# RPi_Extension_EtherCat_Host.net
KiCad netlist of a schematic drawn in EAGLE
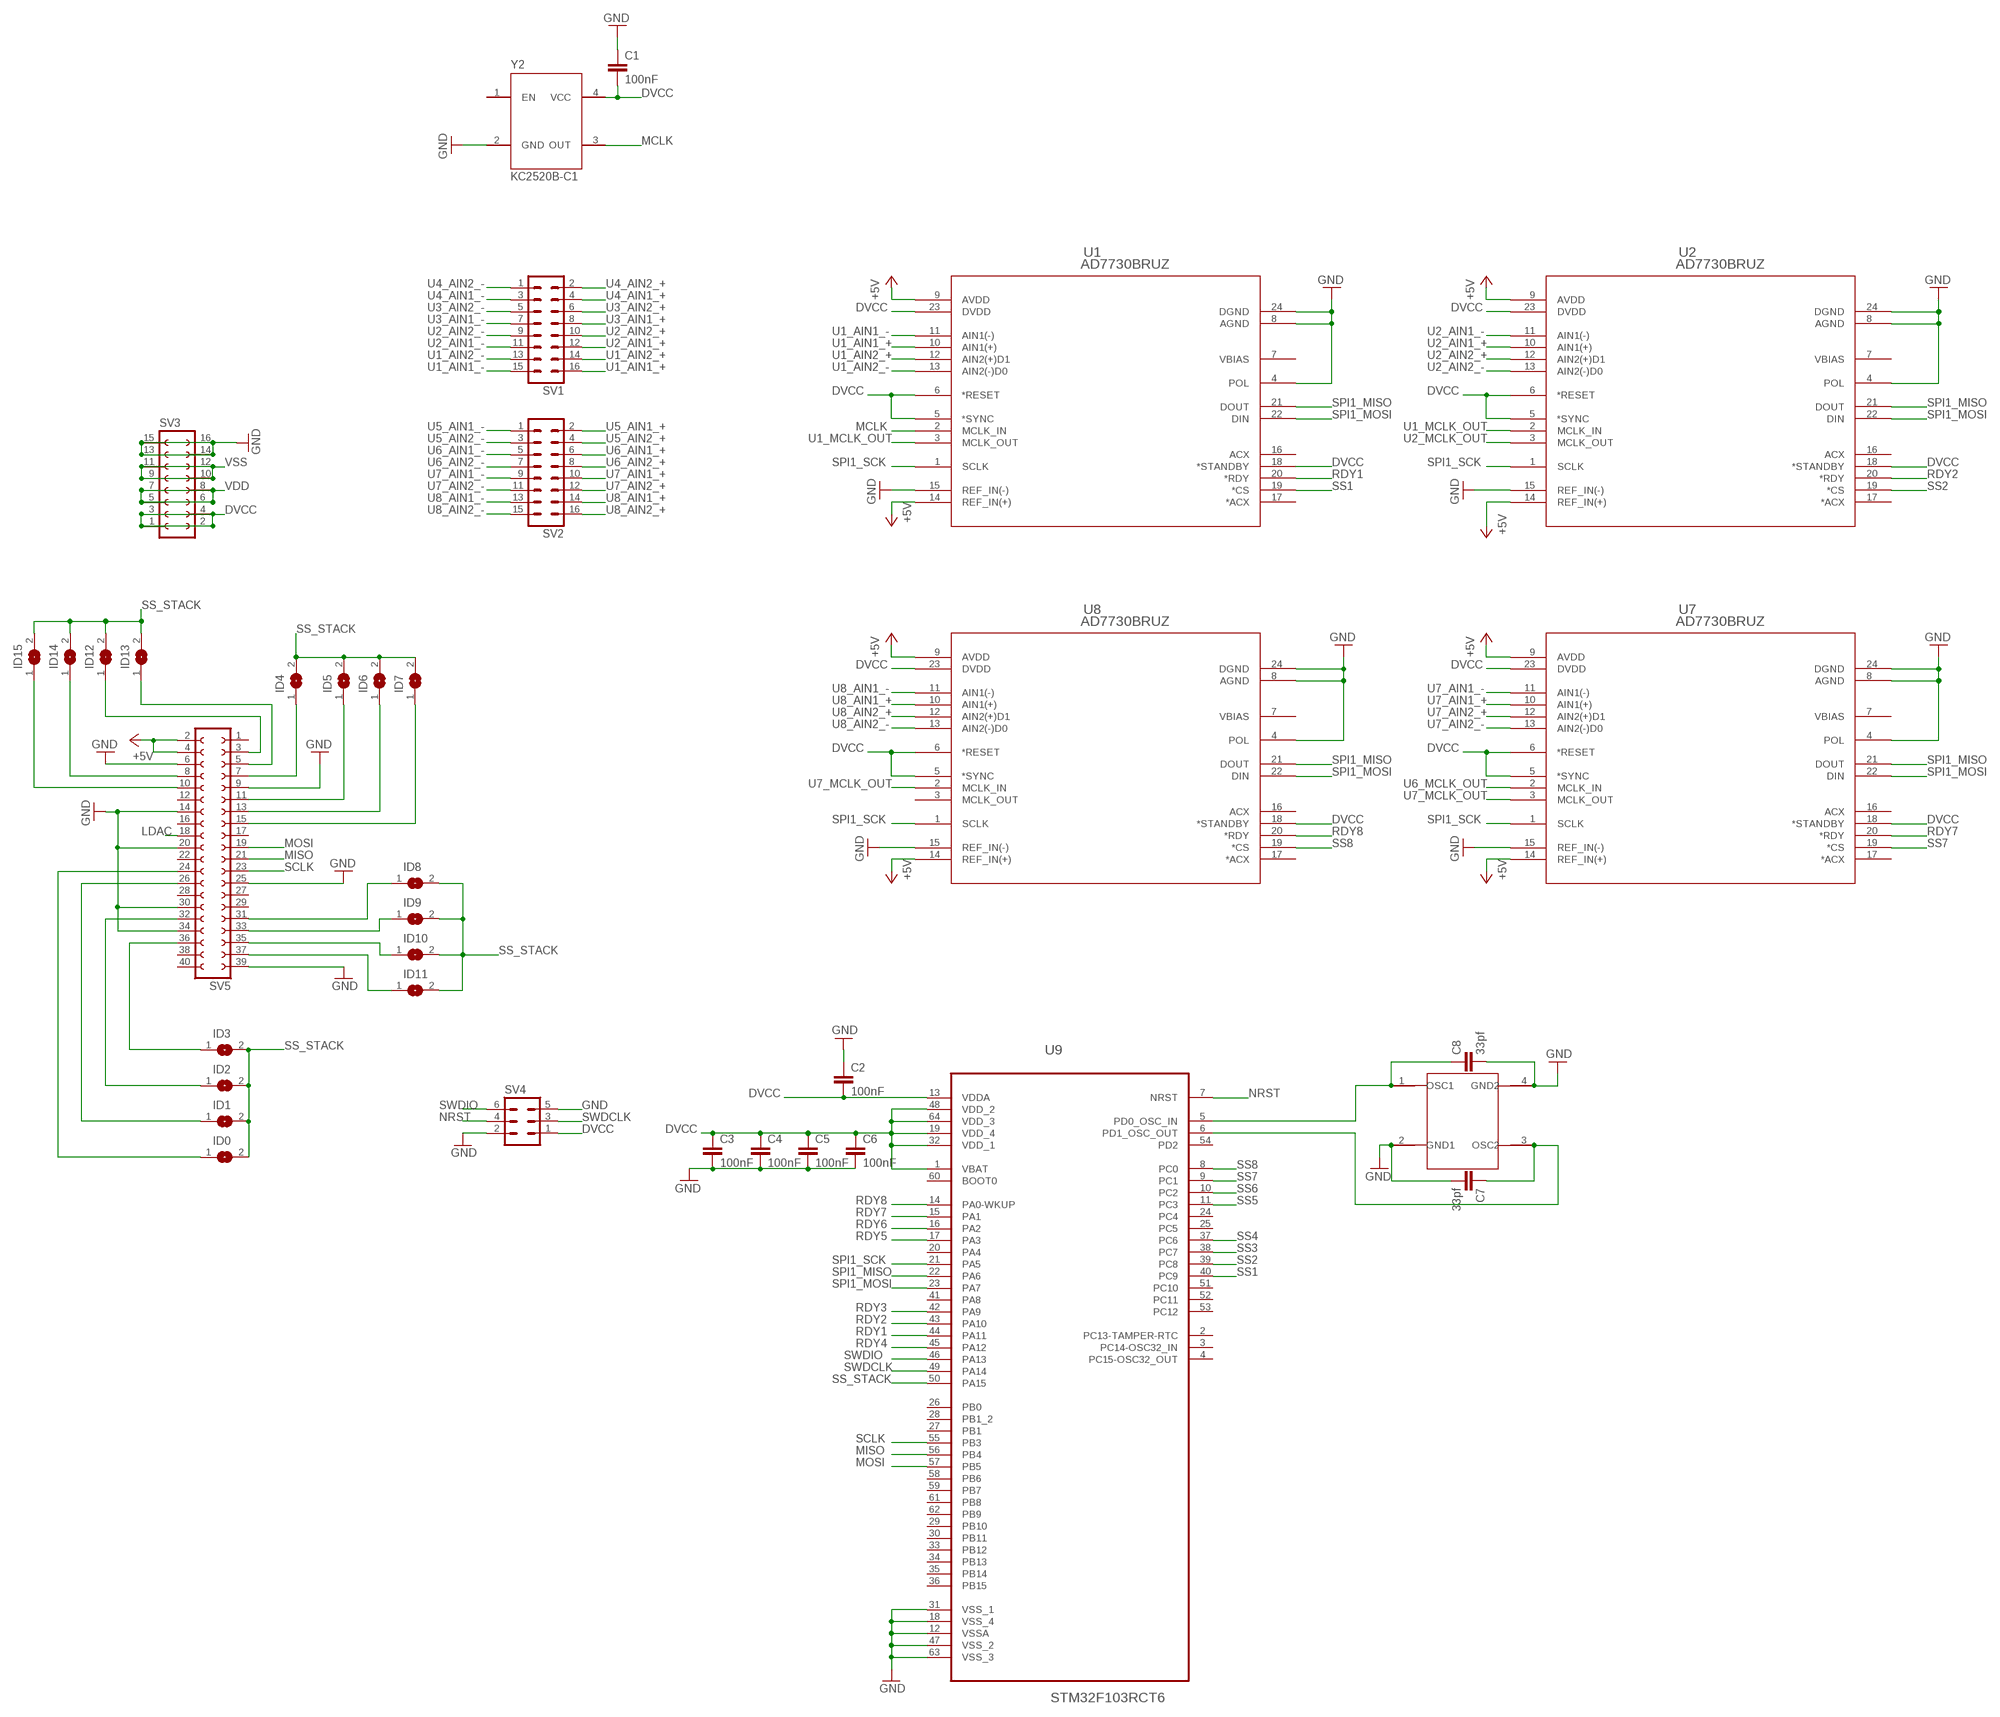
[diagram p0: schematic, sheet 1, part 1 of 2]
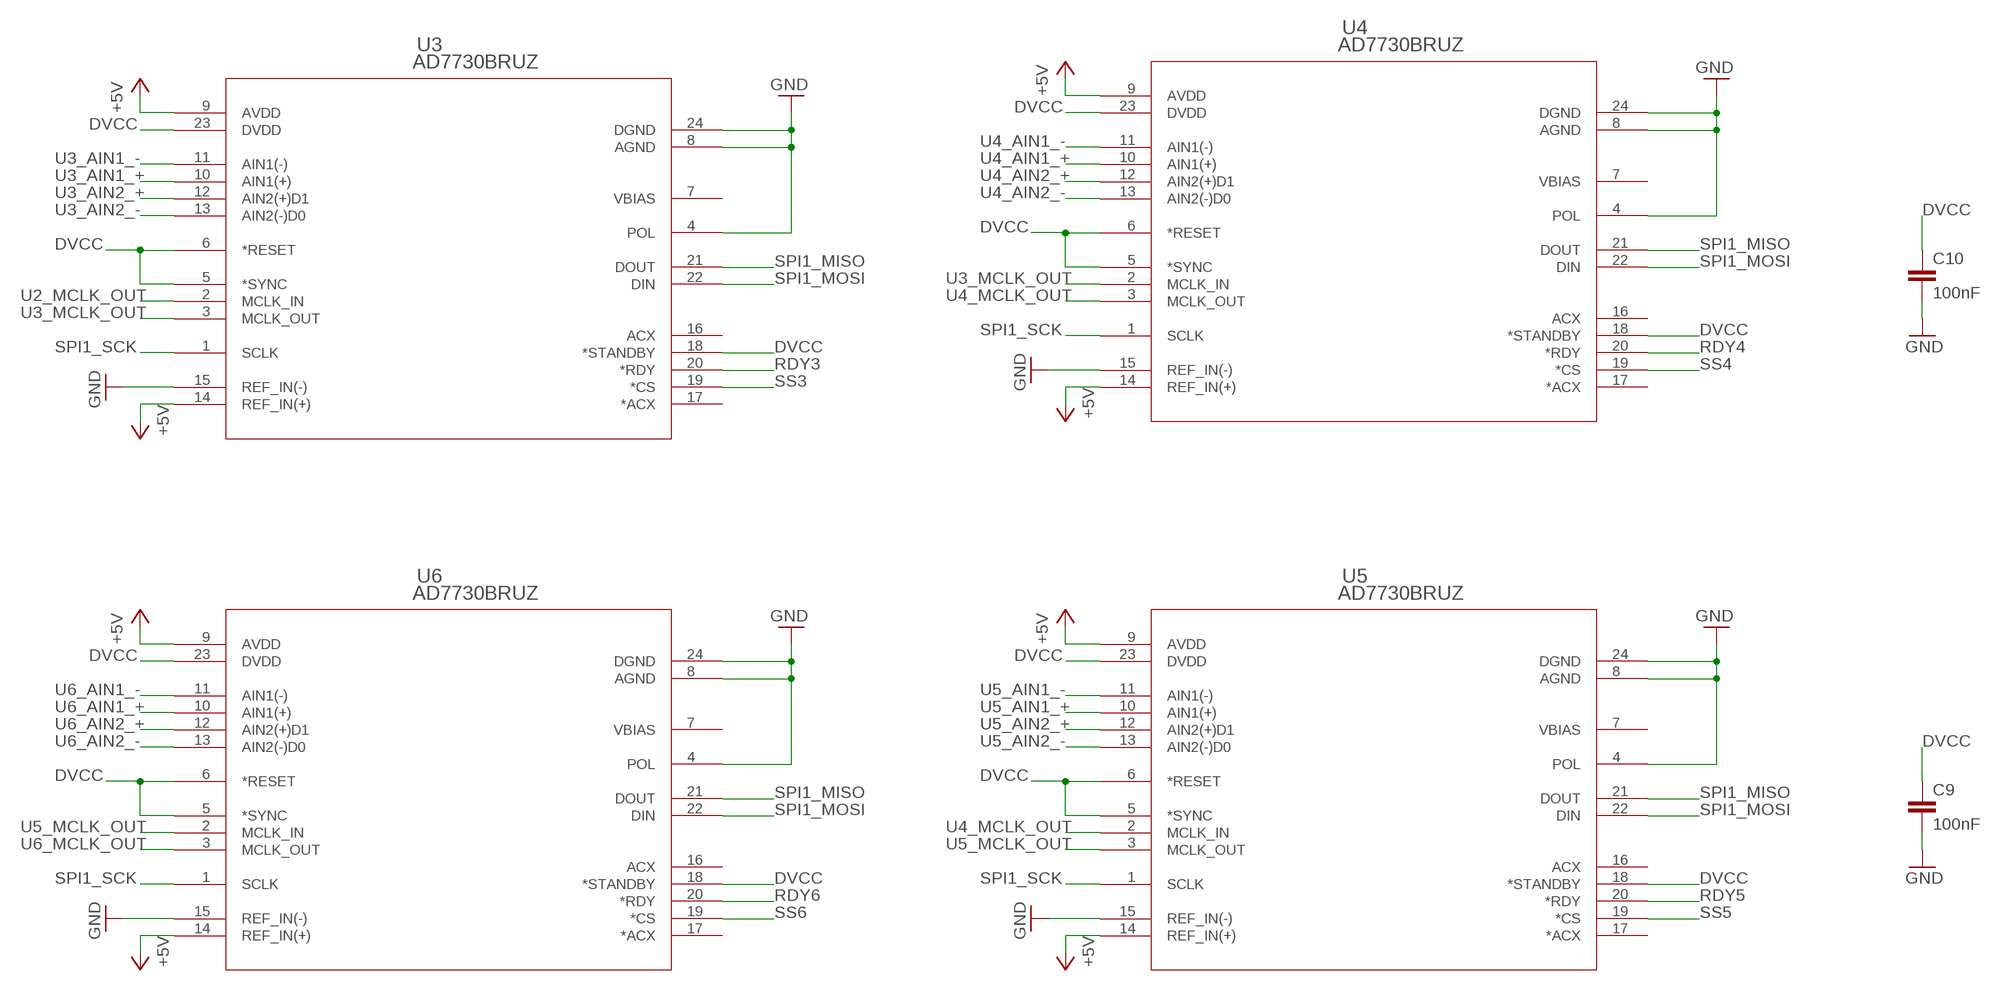
[diagram p1: schematic, sheet 1, part 2 of 2]

(export (version "E")
  (design (tool "Eeschema 10.0.6"))
  (components
    (comp (ref "C1")
      (value "100nF")
      (footprint "eagle-import:C0603")
      (libsource (lib "eagle-import") (part "C-EUC0603"))
    )
    (comp (ref "C2")
      (value "100nF")
      (footprint "eagle-import:C0603")
      (libsource (lib "eagle-import") (part "C-EUC0603"))
    )
    (comp (ref "C3")
      (value "100nF")
      (footprint "eagle-import:C0603")
      (libsource (lib "eagle-import") (part "C-EUC0603"))
    )
    (comp (ref "C4")
      (value "100nF")
      (footprint "eagle-import:C0603")
      (libsource (lib "eagle-import") (part "C-EUC0603"))
    )
    (comp (ref "C5")
      (value "100nF")
      (footprint "eagle-import:C0603")
      (libsource (lib "eagle-import") (part "C-EUC0603"))
    )
    (comp (ref "C6")
      (value "100nF")
      (footprint "eagle-import:C0603")
      (libsource (lib "eagle-import") (part "C-EUC0603"))
    )
    (comp (ref "C7")
      (value "33pf")
      (footprint "eagle-import:C0603")
      (libsource (lib "eagle-import") (part "C-EUC0603"))
    )
    (comp (ref "C8")
      (value "33pf")
      (footprint "eagle-import:C0603")
      (libsource (lib "eagle-import") (part "C-EUC0603"))
    )
    (comp (ref "C9")
      (value "100nF")
      (footprint "eagle-import:C0603")
      (libsource (lib "eagle-import") (part "C-EUC0603"))
    )
    (comp (ref "C10")
      (value "100nF")
      (footprint "eagle-import:C0603")
      (libsource (lib "eagle-import") (part "C-EUC0603"))
    )
    (comp (ref "ID0") (value "SJ") (footprint "eagle-import:SJ") (libsource (lib "eagle-import") (part "SJ")))
    (comp (ref "ID1") (value "SJ") (footprint "eagle-import:SJ") (libsource (lib "eagle-import") (part "SJ")))
    (comp (ref "ID2") (value "SJ") (footprint "eagle-import:SJ") (libsource (lib "eagle-import") (part "SJ")))
    (comp (ref "ID3") (value "SJ") (footprint "eagle-import:SJ") (libsource (lib "eagle-import") (part "SJ")))
    (comp (ref "ID4") (value "SJ") (footprint "eagle-import:SJ") (libsource (lib "eagle-import") (part "SJ")))
    (comp (ref "ID5") (value "SJ") (footprint "eagle-import:SJ") (libsource (lib "eagle-import") (part "SJ")))
    (comp (ref "ID6") (value "SJ") (footprint "eagle-import:SJ") (libsource (lib "eagle-import") (part "SJ")))
    (comp (ref "ID7") (value "SJ") (footprint "eagle-import:SJ") (libsource (lib "eagle-import") (part "SJ")))
    (comp (ref "ID8") (value "SJ") (footprint "eagle-import:SJ") (libsource (lib "eagle-import") (part "SJ")))
    (comp (ref "ID9") (value "SJ") (footprint "eagle-import:SJ") (libsource (lib "eagle-import") (part "SJ")))
    (comp (ref "ID10")
      (value "SJ")
      (footprint "eagle-import:SJ")
      (libsource (lib "eagle-import") (part "SJ"))
    )
    (comp (ref "ID11")
      (value "SJ")
      (footprint "eagle-import:SJ")
      (libsource (lib "eagle-import") (part "SJ"))
    )
    (comp (ref "ID12")
      (value "SJ")
      (footprint "eagle-import:SJ")
      (libsource (lib "eagle-import") (part "SJ"))
    )
    (comp (ref "ID13")
      (value "SJ")
      (footprint "eagle-import:SJ")
      (libsource (lib "eagle-import") (part "SJ"))
    )
    (comp (ref "ID14")
      (value "SJ")
      (footprint "eagle-import:SJ")
      (libsource (lib "eagle-import") (part "SJ"))
    )
    (comp (ref "ID15")
      (value "SJ")
      (footprint "eagle-import:SJ")
      (libsource (lib "eagle-import") (part "SJ"))
    )
    (comp (ref "SV1")
      (value "MA08-2W")
      (footprint "eagle-import:MA08-2W")
      (libsource (lib "eagle-import") (part "MA08-2W"))
    )
    (comp (ref "SV2")
      (value "MA08-2W")
      (footprint "eagle-import:MA08-2W")
      (libsource (lib "eagle-import") (part "MA08-2W"))
    )
    (comp (ref "SV3")
      (value "FE08-2")
      (footprint "eagle-import:FE08-2")
      (libsource (lib "eagle-import") (part "FE08-2"))
    )
    (comp (ref "SV4")
      (value "MA03-2")
      (footprint "eagle-import:MA03-2")
      (libsource (lib "eagle-import") (part "MA03-2"))
    )
    (comp (ref "SV5")
      (value "FE20-2")
      (footprint "eagle-import:FE20-2")
      (libsource (lib "eagle-import") (part "FE20-2"))
    )
    (comp (ref "U1")
      (value "AD7730BRUZ")
      (footprint "eagle-import:RU_24")
      (libsource (lib "eagle-import") (part "AD7730BRUZ"))
    )
    (comp (ref "U2")
      (value "AD7730BRUZ")
      (footprint "eagle-import:RU_24")
      (libsource (lib "eagle-import") (part "AD7730BRUZ"))
    )
    (comp (ref "U3")
      (value "AD7730BRUZ")
      (footprint "eagle-import:RU_24")
      (libsource (lib "eagle-import") (part "AD7730BRUZ"))
    )
    (comp (ref "U4")
      (value "AD7730BRUZ")
      (footprint "eagle-import:RU_24")
      (libsource (lib "eagle-import") (part "AD7730BRUZ"))
    )
    (comp (ref "U5")
      (value "AD7730BRUZ")
      (footprint "eagle-import:RU_24")
      (libsource (lib "eagle-import") (part "AD7730BRUZ"))
    )
    (comp (ref "U6")
      (value "AD7730BRUZ")
      (footprint "eagle-import:RU_24")
      (libsource (lib "eagle-import") (part "AD7730BRUZ"))
    )
    (comp (ref "U7")
      (value "AD7730BRUZ")
      (footprint "eagle-import:RU_24")
      (libsource (lib "eagle-import") (part "AD7730BRUZ"))
    )
    (comp (ref "U8")
      (value "AD7730BRUZ")
      (footprint "eagle-import:RU_24")
      (libsource (lib "eagle-import") (part "AD7730BRUZ"))
    )
    (comp (ref "U9")
      (value "STM32F103RCT6")
      (footprint "eagle-import:QFP50P1200X1200X160-64N")
      (libsource (lib "eagle-import") (part "STM32F103RCT6"))
    )
    (comp (ref "Y1")
      (value "ABM3B")
      (footprint "eagle-import:ABM3B")
      (libsource (lib "eagle-import") (part "ABM3B"))
    )
    (comp (ref "Y2")
      (value "KC2520B-C1")
      (footprint "eagle-import:KC2520B-C1")
      (libsource (lib "eagle-import") (part "KC2520B-C1"))
    )
  )
  (nets
    (net (code "1") (name "+5V") (class "Default")
      (node (ref "SV5") (pin "2") (pinfunction "2_2") (pintype "passive"))
      (node (ref "SV5") (pin "4") (pinfunction "4_4") (pintype "passive"))
      (node (ref "U1") (pin "14") (pinfunction "REF_IN(+)_14") (pintype "passive"))
      (node (ref "U1") (pin "9") (pinfunction "AVDD_9") (pintype "passive"))
      (node (ref "U2") (pin "14") (pinfunction "REF_IN(+)_14") (pintype "passive"))
      (node (ref "U2") (pin "9") (pinfunction "AVDD_9") (pintype "passive"))
      (node (ref "U3") (pin "14") (pinfunction "REF_IN(+)_14") (pintype "passive"))
      (node (ref "U3") (pin "9") (pinfunction "AVDD_9") (pintype "passive"))
      (node (ref "U4") (pin "14") (pinfunction "REF_IN(+)_14") (pintype "passive"))
      (node (ref "U4") (pin "9") (pinfunction "AVDD_9") (pintype "passive"))
      (node (ref "U5") (pin "14") (pinfunction "REF_IN(+)_14") (pintype "passive"))
      (node (ref "U5") (pin "9") (pinfunction "AVDD_9") (pintype "passive"))
      (node (ref "U6") (pin "14") (pinfunction "REF_IN(+)_14") (pintype "passive"))
      (node (ref "U6") (pin "9") (pinfunction "AVDD_9") (pintype "passive"))
      (node (ref "U7") (pin "14") (pinfunction "REF_IN(+)_14") (pintype "passive"))
      (node (ref "U7") (pin "9") (pinfunction "AVDD_9") (pintype "passive"))
      (node (ref "U8") (pin "14") (pinfunction "REF_IN(+)_14") (pintype "passive"))
      (node (ref "U8") (pin "9") (pinfunction "AVDD_9") (pintype "passive"))
    )
    (net (code "2") (name "/DVCC") (class "Default")
      (node (ref "C1") (pin "2") (pinfunction "2_2") (pintype "passive"))
      (node (ref "C10") (pin "1") (pinfunction "1_1") (pintype "passive"))
      (node (ref "C2") (pin "2") (pinfunction "2_2") (pintype "passive"))
      (node (ref "C3") (pin "1") (pinfunction "1_1") (pintype "passive"))
      (node (ref "C4") (pin "1") (pinfunction "1_1") (pintype "passive"))
      (node (ref "C5") (pin "1") (pinfunction "1_1") (pintype "passive"))
      (node (ref "C6") (pin "1") (pinfunction "1_1") (pintype "passive"))
      (node (ref "C9") (pin "1") (pinfunction "1_1") (pintype "passive"))
      (node (ref "SV3") (pin "1") (pinfunction "1_1") (pintype "passive"))
      (node (ref "SV3") (pin "2") (pinfunction "2_2") (pintype "passive"))
      (node (ref "SV3") (pin "3") (pinfunction "3_3") (pintype "passive"))
      (node (ref "SV3") (pin "4") (pinfunction "4_4") (pintype "passive"))
      (node (ref "SV4") (pin "1") (pinfunction "1_1") (pintype "passive"))
      (node (ref "U1") (pin "18") (pinfunction "*STANDBY_18") (pintype "passive"))
      (node (ref "U1") (pin "23") (pinfunction "DVDD_23") (pintype "passive"))
      (node (ref "U1") (pin "5") (pinfunction "*SYNC_5") (pintype "passive"))
      (node (ref "U1") (pin "6") (pinfunction "*RESET_6") (pintype "passive"))
      (node (ref "U2") (pin "18") (pinfunction "*STANDBY_18") (pintype "passive"))
      (node (ref "U2") (pin "23") (pinfunction "DVDD_23") (pintype "passive"))
      (node (ref "U2") (pin "5") (pinfunction "*SYNC_5") (pintype "passive"))
      (node (ref "U2") (pin "6") (pinfunction "*RESET_6") (pintype "passive"))
      (node (ref "U3") (pin "18") (pinfunction "*STANDBY_18") (pintype "passive"))
      (node (ref "U3") (pin "23") (pinfunction "DVDD_23") (pintype "passive"))
      (node (ref "U3") (pin "5") (pinfunction "*SYNC_5") (pintype "passive"))
      (node (ref "U3") (pin "6") (pinfunction "*RESET_6") (pintype "passive"))
      (node (ref "U4") (pin "18") (pinfunction "*STANDBY_18") (pintype "passive"))
      (node (ref "U4") (pin "23") (pinfunction "DVDD_23") (pintype "passive"))
      (node (ref "U4") (pin "5") (pinfunction "*SYNC_5") (pintype "passive"))
      (node (ref "U4") (pin "6") (pinfunction "*RESET_6") (pintype "passive"))
      (node (ref "U5") (pin "18") (pinfunction "*STANDBY_18") (pintype "passive"))
      (node (ref "U5") (pin "23") (pinfunction "DVDD_23") (pintype "passive"))
      (node (ref "U5") (pin "5") (pinfunction "*SYNC_5") (pintype "passive"))
      (node (ref "U5") (pin "6") (pinfunction "*RESET_6") (pintype "passive"))
      (node (ref "U6") (pin "18") (pinfunction "*STANDBY_18") (pintype "passive"))
      (node (ref "U6") (pin "23") (pinfunction "DVDD_23") (pintype "passive"))
      (node (ref "U6") (pin "5") (pinfunction "*SYNC_5") (pintype "passive"))
      (node (ref "U6") (pin "6") (pinfunction "*RESET_6") (pintype "passive"))
      (node (ref "U7") (pin "18") (pinfunction "*STANDBY_18") (pintype "passive"))
      (node (ref "U7") (pin "23") (pinfunction "DVDD_23") (pintype "passive"))
      (node (ref "U7") (pin "5") (pinfunction "*SYNC_5") (pintype "passive"))
      (node (ref "U7") (pin "6") (pinfunction "*RESET_6") (pintype "passive"))
      (node (ref "U8") (pin "18") (pinfunction "*STANDBY_18") (pintype "passive"))
      (node (ref "U8") (pin "23") (pinfunction "DVDD_23") (pintype "passive"))
      (node (ref "U8") (pin "5") (pinfunction "*SYNC_5") (pintype "passive"))
      (node (ref "U8") (pin "6") (pinfunction "*RESET_6") (pintype "passive"))
      (node (ref "U9") (pin "1") (pinfunction "VBAT_1") (pintype "input"))
      (node (ref "U9") (pin "13") (pinfunction "VDDA_13") (pintype "power_in"))
      (node (ref "U9") (pin "19") (pinfunction "VDD_4_19") (pintype "power_in"))
      (node (ref "U9") (pin "32") (pinfunction "VDD_1_32") (pintype "power_in"))
      (node (ref "U9") (pin "48") (pinfunction "VDD_2_48") (pintype "power_in"))
      (node (ref "U9") (pin "64") (pinfunction "VDD_3_64") (pintype "power_in"))
      (node (ref "Y2") (pin "4") (pinfunction "VCC_4") (pintype "bidirectional"))
    )
    (net (code "3") (name "/LDAC") (class "Default")
      (node (ref "SV5") (pin "18") (pinfunction "18_18") (pintype "passive"))
    )
    (net (code "4") (name "/MCLK") (class "Default")
      (node (ref "U1") (pin "2") (pinfunction "MCLK_IN_2") (pintype "passive"))
      (node (ref "Y2") (pin "3") (pinfunction "OUT_3") (pintype "bidirectional"))
    )
    (net (code "5") (name "/MISO") (class "Default")
      (node (ref "SV5") (pin "21") (pinfunction "21_21") (pintype "passive"))
      (node (ref "U9") (pin "56") (pinfunction "PB4_56") (pintype "bidirectional"))
    )
    (net (code "6") (name "/MOSI") (class "Default")
      (node (ref "SV5") (pin "19") (pinfunction "19_19") (pintype "passive"))
      (node (ref "U9") (pin "57") (pinfunction "PB5_57") (pintype "bidirectional"))
    )
    (net (code "7") (name "/NRST") (class "Default")
      (node (ref "SV4") (pin "4") (pinfunction "4_4") (pintype "passive"))
      (node (ref "U9") (pin "7") (pinfunction "NRST_7") (pintype "output"))
    )
    (net (code "8") (name "/PB7") (class "Default")
      (node (ref "U9") (pin "59") (pinfunction "PB7_59") (pintype "power_in"))
    )
    (net (code "9") (name "/RDY1") (class "Default")
      (node (ref "U1") (pin "20") (pinfunction "*RDY_20") (pintype "passive"))
      (node (ref "U9") (pin "44") (pinfunction "PA11_44") (pintype "bidirectional"))
    )
    (net (code "10") (name "/RDY2") (class "Default")
      (node (ref "U2") (pin "20") (pinfunction "*RDY_20") (pintype "passive"))
      (node (ref "U9") (pin "43") (pinfunction "PA10_43") (pintype "bidirectional"))
    )
    (net (code "11") (name "/RDY3") (class "Default")
      (node (ref "U3") (pin "20") (pinfunction "*RDY_20") (pintype "passive"))
      (node (ref "U9") (pin "42") (pinfunction "PA9_42") (pintype "bidirectional"))
    )
    (net (code "12") (name "/RDY4") (class "Default")
      (node (ref "U4") (pin "20") (pinfunction "*RDY_20") (pintype "passive"))
      (node (ref "U9") (pin "45") (pinfunction "PA12_45") (pintype "bidirectional"))
    )
    (net (code "13") (name "/RDY5") (class "Default")
      (node (ref "U5") (pin "20") (pinfunction "*RDY_20") (pintype "passive"))
      (node (ref "U9") (pin "17") (pinfunction "PA3_17") (pintype "bidirectional"))
    )
    (net (code "14") (name "/RDY6") (class "Default")
      (node (ref "U6") (pin "20") (pinfunction "*RDY_20") (pintype "passive"))
      (node (ref "U9") (pin "16") (pinfunction "PA2_16") (pintype "bidirectional"))
    )
    (net (code "15") (name "/RDY7") (class "Default")
      (node (ref "U7") (pin "20") (pinfunction "*RDY_20") (pintype "passive"))
      (node (ref "U9") (pin "15") (pinfunction "PA1_15") (pintype "bidirectional"))
    )
    (net (code "16") (name "/RDY8") (class "Default")
      (node (ref "U8") (pin "20") (pinfunction "*RDY_20") (pintype "passive"))
      (node (ref "U9") (pin "14") (pinfunction "PA0-WKUP_14") (pintype "bidirectional"))
    )
    (net (code "17") (name "/SCLK") (class "Default")
      (node (ref "SV5") (pin "23") (pinfunction "23_23") (pintype "passive"))
      (node (ref "U9") (pin "55") (pinfunction "PB3_55") (pintype "bidirectional"))
    )
    (net (code "18") (name "/SPI1_MISO") (class "Default")
      (node (ref "U1") (pin "21") (pinfunction "DOUT_21") (pintype "passive"))
      (node (ref "U2") (pin "21") (pinfunction "DOUT_21") (pintype "passive"))
      (node (ref "U3") (pin "21") (pinfunction "DOUT_21") (pintype "passive"))
      (node (ref "U4") (pin "21") (pinfunction "DOUT_21") (pintype "passive"))
      (node (ref "U5") (pin "21") (pinfunction "DOUT_21") (pintype "passive"))
      (node (ref "U6") (pin "21") (pinfunction "DOUT_21") (pintype "passive"))
      (node (ref "U7") (pin "21") (pinfunction "DOUT_21") (pintype "passive"))
      (node (ref "U8") (pin "21") (pinfunction "DOUT_21") (pintype "passive"))
      (node (ref "U9") (pin "22") (pinfunction "PA6_22") (pintype "bidirectional"))
    )
    (net (code "19") (name "/SPI1_MOSI") (class "Default")
      (node (ref "U1") (pin "22") (pinfunction "DIN_22") (pintype "passive"))
      (node (ref "U2") (pin "22") (pinfunction "DIN_22") (pintype "passive"))
      (node (ref "U3") (pin "22") (pinfunction "DIN_22") (pintype "passive"))
      (node (ref "U4") (pin "22") (pinfunction "DIN_22") (pintype "passive"))
      (node (ref "U5") (pin "22") (pinfunction "DIN_22") (pintype "passive"))
      (node (ref "U6") (pin "22") (pinfunction "DIN_22") (pintype "passive"))
      (node (ref "U7") (pin "22") (pinfunction "DIN_22") (pintype "passive"))
      (node (ref "U8") (pin "22") (pinfunction "DIN_22") (pintype "passive"))
      (node (ref "U9") (pin "23") (pinfunction "PA7_23") (pintype "power_in"))
    )
    (net (code "20") (name "/SPI1_SCK") (class "Default")
      (node (ref "U1") (pin "1") (pinfunction "SCLK_1") (pintype "passive"))
      (node (ref "U2") (pin "1") (pinfunction "SCLK_1") (pintype "passive"))
      (node (ref "U3") (pin "1") (pinfunction "SCLK_1") (pintype "passive"))
      (node (ref "U4") (pin "1") (pinfunction "SCLK_1") (pintype "passive"))
      (node (ref "U5") (pin "1") (pinfunction "SCLK_1") (pintype "passive"))
      (node (ref "U6") (pin "1") (pinfunction "SCLK_1") (pintype "passive"))
      (node (ref "U7") (pin "1") (pinfunction "SCLK_1") (pintype "passive"))
      (node (ref "U8") (pin "1") (pinfunction "SCLK_1") (pintype "passive"))
      (node (ref "U9") (pin "21") (pinfunction "PA5_21") (pintype "bidirectional"))
    )
    (net (code "21") (name "/SS1") (class "Default")
      (node (ref "U1") (pin "19") (pinfunction "*CS_19") (pintype "passive"))
      (node (ref "U9") (pin "40") (pinfunction "PC9_40") (pintype "bidirectional"))
    )
    (net (code "22") (name "/SS2") (class "Default")
      (node (ref "U2") (pin "19") (pinfunction "*CS_19") (pintype "passive"))
      (node (ref "U9") (pin "39") (pinfunction "PC8_39") (pintype "bidirectional"))
    )
    (net (code "23") (name "/SS3") (class "Default")
      (node (ref "U3") (pin "19") (pinfunction "*CS_19") (pintype "passive"))
      (node (ref "U9") (pin "38") (pinfunction "PC7_38") (pintype "bidirectional"))
    )
    (net (code "24") (name "/SS4") (class "Default")
      (node (ref "U4") (pin "19") (pinfunction "*CS_19") (pintype "passive"))
      (node (ref "U9") (pin "37") (pinfunction "PC6_37") (pintype "bidirectional"))
    )
    (net (code "25") (name "/SS5") (class "Default")
      (node (ref "U5") (pin "19") (pinfunction "*CS_19") (pintype "passive"))
      (node (ref "U9") (pin "11") (pinfunction "PC3_11") (pintype "bidirectional"))
    )
    (net (code "26") (name "/SS6") (class "Default")
      (node (ref "U6") (pin "19") (pinfunction "*CS_19") (pintype "passive"))
      (node (ref "U9") (pin "10") (pinfunction "PC2_10") (pintype "bidirectional"))
    )
    (net (code "27") (name "/SS7") (class "Default")
      (node (ref "U7") (pin "19") (pinfunction "*CS_19") (pintype "passive"))
      (node (ref "U9") (pin "9") (pinfunction "PC1_9") (pintype "bidirectional"))
    )
    (net (code "28") (name "/SS8") (class "Default")
      (node (ref "U8") (pin "19") (pinfunction "*CS_19") (pintype "passive"))
      (node (ref "U9") (pin "8") (pinfunction "PC0_8") (pintype "bidirectional"))
    )
    (net (code "29") (name "/SS_STACK") (class "Default")
      (node (ref "ID0") (pin "2") (pinfunction "2_2") (pintype "passive"))
      (node (ref "ID1") (pin "2") (pinfunction "2_2") (pintype "passive"))
      (node (ref "ID10") (pin "2") (pinfunction "2_2") (pintype "passive"))
      (node (ref "ID11") (pin "2") (pinfunction "2_2") (pintype "passive"))
      (node (ref "ID12") (pin "2") (pinfunction "2_2") (pintype "passive"))
      (node (ref "ID13") (pin "2") (pinfunction "2_2") (pintype "passive"))
      (node (ref "ID14") (pin "2") (pinfunction "2_2") (pintype "passive"))
      (node (ref "ID15") (pin "2") (pinfunction "2_2") (pintype "passive"))
      (node (ref "ID2") (pin "2") (pinfunction "2_2") (pintype "passive"))
      (node (ref "ID3") (pin "2") (pinfunction "2_2") (pintype "passive"))
      (node (ref "ID4") (pin "2") (pinfunction "2_2") (pintype "passive"))
      (node (ref "ID5") (pin "2") (pinfunction "2_2") (pintype "passive"))
      (node (ref "ID6") (pin "2") (pinfunction "2_2") (pintype "passive"))
      (node (ref "ID7") (pin "2") (pinfunction "2_2") (pintype "passive"))
      (node (ref "ID8") (pin "2") (pinfunction "2_2") (pintype "passive"))
      (node (ref "ID9") (pin "2") (pinfunction "2_2") (pintype "passive"))
      (node (ref "U9") (pin "50") (pinfunction "PA15_50") (pintype "bidirectional"))
    )
    (net (code "30") (name "/SWDCLK") (class "Default")
      (node (ref "SV4") (pin "3") (pinfunction "3_3") (pintype "passive"))
      (node (ref "U9") (pin "49") (pinfunction "PA14_49") (pintype "bidirectional"))
    )
    (net (code "31") (name "/SWDIO") (class "Default")
      (node (ref "SV4") (pin "6") (pinfunction "6_6") (pintype "passive"))
      (node (ref "U9") (pin "46") (pinfunction "PA13_46") (pintype "bidirectional"))
    )
    (net (code "32") (name "/U1_AIN1_+") (class "Default")
      (node (ref "SV1") (pin "16") (pinfunction "16_16") (pintype "passive"))
      (node (ref "U1") (pin "10") (pinfunction "AIN1(+)_10") (pintype "passive"))
    )
    (net (code "33") (name "/U1_AIN1_-") (class "Default")
      (node (ref "SV1") (pin "15") (pinfunction "15_15") (pintype "passive"))
      (node (ref "U1") (pin "11") (pinfunction "AIN1(-)_11") (pintype "passive"))
    )
    (net (code "34") (name "/U1_AIN2_+") (class "Default")
      (node (ref "SV1") (pin "14") (pinfunction "14_14") (pintype "passive"))
      (node (ref "U1") (pin "12") (pinfunction "AIN2(+)D1_12") (pintype "passive"))
    )
    (net (code "35") (name "/U1_AIN2_-") (class "Default")
      (node (ref "SV1") (pin "13") (pinfunction "13_13") (pintype "passive"))
      (node (ref "U1") (pin "13") (pinfunction "AIN2(-)D0_13") (pintype "passive"))
    )
    (net (code "36") (name "/U1_MCLK_OUT") (class "Default")
      (node (ref "U1") (pin "3") (pinfunction "MCLK_OUT_3") (pintype "passive"))
      (node (ref "U2") (pin "2") (pinfunction "MCLK_IN_2") (pintype "passive"))
    )
    (net (code "37") (name "/U2_AIN1_+") (class "Default")
      (node (ref "SV1") (pin "12") (pinfunction "12_12") (pintype "passive"))
      (node (ref "U2") (pin "10") (pinfunction "AIN1(+)_10") (pintype "passive"))
    )
    (net (code "38") (name "/U2_AIN1_-") (class "Default")
      (node (ref "SV1") (pin "11") (pinfunction "11_11") (pintype "passive"))
      (node (ref "U2") (pin "11") (pinfunction "AIN1(-)_11") (pintype "passive"))
    )
    (net (code "39") (name "/U2_AIN2_+") (class "Default")
      (node (ref "SV1") (pin "10") (pinfunction "10_10") (pintype "passive"))
      (node (ref "U2") (pin "12") (pinfunction "AIN2(+)D1_12") (pintype "passive"))
    )
    (net (code "40") (name "/U2_AIN2_-") (class "Default")
      (node (ref "SV1") (pin "9") (pinfunction "9_9") (pintype "passive"))
      (node (ref "U2") (pin "13") (pinfunction "AIN2(-)D0_13") (pintype "passive"))
    )
    (net (code "41") (name "/U2_MCLK_OUT") (class "Default")
      (node (ref "U2") (pin "3") (pinfunction "MCLK_OUT_3") (pintype "passive"))
      (node (ref "U3") (pin "2") (pinfunction "MCLK_IN_2") (pintype "passive"))
    )
    (net (code "42") (name "/U3_AIN1_+") (class "Default")
      (node (ref "SV1") (pin "8") (pinfunction "8_8") (pintype "passive"))
      (node (ref "U3") (pin "10") (pinfunction "AIN1(+)_10") (pintype "passive"))
    )
    (net (code "43") (name "/U3_AIN1_-") (class "Default")
      (node (ref "SV1") (pin "7") (pinfunction "7_7") (pintype "passive"))
      (node (ref "U3") (pin "11") (pinfunction "AIN1(-)_11") (pintype "passive"))
    )
    (net (code "44") (name "/U3_AIN2_+") (class "Default")
      (node (ref "SV1") (pin "6") (pinfunction "6_6") (pintype "passive"))
      (node (ref "U3") (pin "12") (pinfunction "AIN2(+)D1_12") (pintype "passive"))
    )
    (net (code "45") (name "/U3_AIN2_-") (class "Default")
      (node (ref "SV1") (pin "5") (pinfunction "5_5") (pintype "passive"))
      (node (ref "U3") (pin "13") (pinfunction "AIN2(-)D0_13") (pintype "passive"))
    )
    (net (code "46") (name "/U3_MCLK_OUT") (class "Default")
      (node (ref "U3") (pin "3") (pinfunction "MCLK_OUT_3") (pintype "passive"))
      (node (ref "U4") (pin "2") (pinfunction "MCLK_IN_2") (pintype "passive"))
    )
    (net (code "47") (name "/U4_AIN1_+") (class "Default")
      (node (ref "SV1") (pin "4") (pinfunction "4_4") (pintype "passive"))
      (node (ref "U4") (pin "10") (pinfunction "AIN1(+)_10") (pintype "passive"))
    )
    (net (code "48") (name "/U4_AIN1_-") (class "Default")
      (node (ref "SV1") (pin "3") (pinfunction "3_3") (pintype "passive"))
      (node (ref "U4") (pin "11") (pinfunction "AIN1(-)_11") (pintype "passive"))
    )
    (net (code "49") (name "/U4_AIN2_+") (class "Default")
      (node (ref "SV1") (pin "2") (pinfunction "2_2") (pintype "passive"))
      (node (ref "U4") (pin "12") (pinfunction "AIN2(+)D1_12") (pintype "passive"))
    )
    (net (code "50") (name "/U4_AIN2_-") (class "Default")
      (node (ref "SV1") (pin "1") (pinfunction "1_1") (pintype "passive"))
      (node (ref "U4") (pin "13") (pinfunction "AIN2(-)D0_13") (pintype "passive"))
    )
    (net (code "51") (name "/U4_MCLK_OUT") (class "Default")
      (node (ref "U4") (pin "3") (pinfunction "MCLK_OUT_3") (pintype "passive"))
      (node (ref "U5") (pin "2") (pinfunction "MCLK_IN_2") (pintype "passive"))
    )
    (net (code "52") (name "/U5_AIN1_+") (class "Default")
      (node (ref "SV2") (pin "2") (pinfunction "2_2") (pintype "passive"))
      (node (ref "U5") (pin "10") (pinfunction "AIN1(+)_10") (pintype "passive"))
    )
    (net (code "53") (name "/U5_AIN1_-") (class "Default")
      (node (ref "SV2") (pin "1") (pinfunction "1_1") (pintype "passive"))
      (node (ref "U5") (pin "11") (pinfunction "AIN1(-)_11") (pintype "passive"))
    )
    (net (code "54") (name "/U5_AIN2_+") (class "Default")
      (node (ref "SV2") (pin "4") (pinfunction "4_4") (pintype "passive"))
      (node (ref "U5") (pin "12") (pinfunction "AIN2(+)D1_12") (pintype "passive"))
    )
    (net (code "55") (name "/U5_AIN2_-") (class "Default")
      (node (ref "SV2") (pin "3") (pinfunction "3_3") (pintype "passive"))
      (node (ref "U5") (pin "13") (pinfunction "AIN2(-)D0_13") (pintype "passive"))
    )
    (net (code "56") (name "/U5_MCLK_OUT") (class "Default")
      (node (ref "U5") (pin "3") (pinfunction "MCLK_OUT_3") (pintype "passive"))
      (node (ref "U6") (pin "2") (pinfunction "MCLK_IN_2") (pintype "passive"))
    )
    (net (code "57") (name "/U6_AIN1_+") (class "Default")
      (node (ref "SV2") (pin "6") (pinfunction "6_6") (pintype "passive"))
      (node (ref "U6") (pin "10") (pinfunction "AIN1(+)_10") (pintype "passive"))
    )
    (net (code "58") (name "/U6_AIN1_-") (class "Default")
      (node (ref "SV2") (pin "5") (pinfunction "5_5") (pintype "passive"))
      (node (ref "U6") (pin "11") (pinfunction "AIN1(-)_11") (pintype "passive"))
    )
    (net (code "59") (name "/U6_AIN2_+") (class "Default")
      (node (ref "SV2") (pin "8") (pinfunction "8_8") (pintype "passive"))
      (node (ref "U6") (pin "12") (pinfunction "AIN2(+)D1_12") (pintype "passive"))
    )
    (net (code "60") (name "/U6_AIN2_-") (class "Default")
      (node (ref "SV2") (pin "7") (pinfunction "7_7") (pintype "passive"))
      (node (ref "U6") (pin "13") (pinfunction "AIN2(-)D0_13") (pintype "passive"))
    )
    (net (code "61") (name "/U6_MCLK_OUT") (class "Default")
      (node (ref "U6") (pin "3") (pinfunction "MCLK_OUT_3") (pintype "passive"))
      (node (ref "U7") (pin "2") (pinfunction "MCLK_IN_2") (pintype "passive"))
    )
    (net (code "62") (name "/U7_AIN1_+") (class "Default")
      (node (ref "SV2") (pin "10") (pinfunction "10_10") (pintype "passive"))
      (node (ref "U7") (pin "10") (pinfunction "AIN1(+)_10") (pintype "passive"))
    )
    (net (code "63") (name "/U7_AIN1_-") (class "Default")
      (node (ref "SV2") (pin "9") (pinfunction "9_9") (pintype "passive"))
      (node (ref "U7") (pin "11") (pinfunction "AIN1(-)_11") (pintype "passive"))
    )
    (net (code "64") (name "/U7_AIN2_+") (class "Default")
      (node (ref "SV2") (pin "12") (pinfunction "12_12") (pintype "passive"))
      (node (ref "U7") (pin "12") (pinfunction "AIN2(+)D1_12") (pintype "passive"))
    )
    (net (code "65") (name "/U7_AIN2_-") (class "Default")
      (node (ref "SV2") (pin "11") (pinfunction "11_11") (pintype "passive"))
      (node (ref "U7") (pin "13") (pinfunction "AIN2(-)D0_13") (pintype "passive"))
    )
    (net (code "66") (name "/U7_MCLK_OUT") (class "Default")
      (node (ref "U7") (pin "3") (pinfunction "MCLK_OUT_3") (pintype "passive"))
      (node (ref "U8") (pin "2") (pinfunction "MCLK_IN_2") (pintype "passive"))
    )
    (net (code "67") (name "/U8_AIN1_+") (class "Default")
      (node (ref "SV2") (pin "14") (pinfunction "14_14") (pintype "passive"))
      (node (ref "U8") (pin "10") (pinfunction "AIN1(+)_10") (pintype "passive"))
    )
    (net (code "68") (name "/U8_AIN1_-") (class "Default")
      (node (ref "SV2") (pin "13") (pinfunction "13_13") (pintype "passive"))
      (node (ref "U8") (pin "11") (pinfunction "AIN1(-)_11") (pintype "passive"))
    )
    (net (code "69") (name "/U8_AIN2_+") (class "Default")
      (node (ref "SV2") (pin "16") (pinfunction "16_16") (pintype "passive"))
      (node (ref "U8") (pin "12") (pinfunction "AIN2(+)D1_12") (pintype "passive"))
    )
    (net (code "70") (name "/U8_AIN2_-") (class "Default")
      (node (ref "SV2") (pin "15") (pinfunction "15_15") (pintype "passive"))
      (node (ref "U8") (pin "13") (pinfunction "AIN2(-)D0_13") (pintype "passive"))
    )
    (net (code "71") (name "/VDD") (class "Default")
      (node (ref "SV3") (pin "5") (pinfunction "5_5") (pintype "passive"))
      (node (ref "SV3") (pin "6") (pinfunction "6_6") (pintype "passive"))
      (node (ref "SV3") (pin "7") (pinfunction "7_7") (pintype "passive"))
      (node (ref "SV3") (pin "8") (pinfunction "8_8") (pintype "passive"))
    )
    (net (code "72") (name "/VSS") (class "Default")
      (node (ref "SV3") (pin "10") (pinfunction "10_10") (pintype "passive"))
      (node (ref "SV3") (pin "11") (pinfunction "11_11") (pintype "passive"))
      (node (ref "SV3") (pin "12") (pinfunction "12_12") (pintype "passive"))
      (node (ref "SV3") (pin "9") (pinfunction "9_9") (pintype "passive"))
    )
    (net (code "73") (name "GND") (class "Default")
      (node (ref "C1") (pin "1") (pinfunction "1_1") (pintype "passive"))
      (node (ref "C10") (pin "2") (pinfunction "2_2") (pintype "passive"))
      (node (ref "C2") (pin "1") (pinfunction "1_1") (pintype "passive"))
      (node (ref "C3") (pin "2") (pinfunction "2_2") (pintype "passive"))
      (node (ref "C4") (pin "2") (pinfunction "2_2") (pintype "passive"))
      (node (ref "C5") (pin "2") (pinfunction "2_2") (pintype "passive"))
      (node (ref "C6") (pin "2") (pinfunction "2_2") (pintype "passive"))
      (node (ref "C7") (pin "2") (pinfunction "2_2") (pintype "passive"))
      (node (ref "C8") (pin "2") (pinfunction "2_2") (pintype "passive"))
      (node (ref "C9") (pin "2") (pinfunction "2_2") (pintype "passive"))
      (node (ref "SV3") (pin "13") (pinfunction "13_13") (pintype "passive"))
      (node (ref "SV3") (pin "14") (pinfunction "14_14") (pintype "passive"))
      (node (ref "SV3") (pin "15") (pinfunction "15_15") (pintype "passive"))
      (node (ref "SV3") (pin "16") (pinfunction "16_16") (pintype "passive"))
      (node (ref "SV4") (pin "2") (pinfunction "2_2") (pintype "passive"))
      (node (ref "SV4") (pin "5") (pinfunction "5_5") (pintype "passive"))
      (node (ref "SV5") (pin "14") (pinfunction "14_14") (pintype "passive"))
      (node (ref "SV5") (pin "20") (pinfunction "20_20") (pintype "passive"))
      (node (ref "SV5") (pin "25") (pinfunction "25_25") (pintype "passive"))
      (node (ref "SV5") (pin "30") (pinfunction "30_30") (pintype "passive"))
      (node (ref "SV5") (pin "34") (pinfunction "34_34") (pintype "passive"))
      (node (ref "SV5") (pin "39") (pinfunction "39_39") (pintype "passive"))
      (node (ref "SV5") (pin "6") (pinfunction "6_6") (pintype "passive"))
      (node (ref "SV5") (pin "9") (pinfunction "9_9") (pintype "passive"))
      (node (ref "U1") (pin "15") (pinfunction "REF_IN(-)_15") (pintype "passive"))
      (node (ref "U1") (pin "24") (pinfunction "DGND_24") (pintype "passive"))
      (node (ref "U1") (pin "4") (pinfunction "POL_4") (pintype "passive"))
      (node (ref "U1") (pin "8") (pinfunction "AGND_8") (pintype "passive"))
      (node (ref "U2") (pin "15") (pinfunction "REF_IN(-)_15") (pintype "passive"))
      (node (ref "U2") (pin "24") (pinfunction "DGND_24") (pintype "passive"))
      (node (ref "U2") (pin "4") (pinfunction "POL_4") (pintype "passive"))
      (node (ref "U2") (pin "8") (pinfunction "AGND_8") (pintype "passive"))
      (node (ref "U3") (pin "15") (pinfunction "REF_IN(-)_15") (pintype "passive"))
      (node (ref "U3") (pin "24") (pinfunction "DGND_24") (pintype "passive"))
      (node (ref "U3") (pin "4") (pinfunction "POL_4") (pintype "passive"))
      (node (ref "U3") (pin "8") (pinfunction "AGND_8") (pintype "passive"))
      (node (ref "U4") (pin "15") (pinfunction "REF_IN(-)_15") (pintype "passive"))
      (node (ref "U4") (pin "24") (pinfunction "DGND_24") (pintype "passive"))
      (node (ref "U4") (pin "4") (pinfunction "POL_4") (pintype "passive"))
      (node (ref "U4") (pin "8") (pinfunction "AGND_8") (pintype "passive"))
      (node (ref "U5") (pin "15") (pinfunction "REF_IN(-)_15") (pintype "passive"))
      (node (ref "U5") (pin "24") (pinfunction "DGND_24") (pintype "passive"))
      (node (ref "U5") (pin "4") (pinfunction "POL_4") (pintype "passive"))
      (node (ref "U5") (pin "8") (pinfunction "AGND_8") (pintype "passive"))
      (node (ref "U6") (pin "15") (pinfunction "REF_IN(-)_15") (pintype "passive"))
      (node (ref "U6") (pin "24") (pinfunction "DGND_24") (pintype "passive"))
      (node (ref "U6") (pin "4") (pinfunction "POL_4") (pintype "passive"))
      (node (ref "U6") (pin "8") (pinfunction "AGND_8") (pintype "passive"))
      (node (ref "U7") (pin "15") (pinfunction "REF_IN(-)_15") (pintype "passive"))
      (node (ref "U7") (pin "24") (pinfunction "DGND_24") (pintype "passive"))
      (node (ref "U7") (pin "4") (pinfunction "POL_4") (pintype "passive"))
      (node (ref "U7") (pin "8") (pinfunction "AGND_8") (pintype "passive"))
      (node (ref "U8") (pin "15") (pinfunction "REF_IN(-)_15") (pintype "passive"))
      (node (ref "U8") (pin "24") (pinfunction "DGND_24") (pintype "passive"))
      (node (ref "U8") (pin "4") (pinfunction "POL_4") (pintype "passive"))
      (node (ref "U8") (pin "8") (pinfunction "AGND_8") (pintype "passive"))
      (node (ref "U9") (pin "12") (pinfunction "VSSA_12") (pintype "passive"))
      (node (ref "U9") (pin "18") (pinfunction "VSS_4_18") (pintype "passive"))
      (node (ref "U9") (pin "31") (pinfunction "VSS_1_31") (pintype "passive"))
      (node (ref "U9") (pin "47") (pinfunction "VSS_2_47") (pintype "passive"))
      (node (ref "U9") (pin "63") (pinfunction "VSS_3_63") (pintype "passive"))
      (node (ref "Y1") (pin "2") (pinfunction "GND1_2") (pintype "bidirectional"))
      (node (ref "Y1") (pin "4") (pinfunction "GND2_4") (pintype "bidirectional"))
      (node (ref "Y2") (pin "2") (pinfunction "GND_2") (pintype "bidirectional"))
    )
    (net (code "74") (name "Net-(ID0-Pad1)") (class "Default")
      (node (ref "ID0") (pin "1") (pinfunction "1_1") (pintype "passive"))
      (node (ref "SV5") (pin "24") (pinfunction "24_24") (pintype "passive"))
    )
    (net (code "75") (name "Net-(ID1-Pad1)") (class "Default")
      (node (ref "ID1") (pin "1") (pinfunction "1_1") (pintype "passive"))
      (node (ref "SV5") (pin "26") (pinfunction "26_26") (pintype "passive"))
    )
    (net (code "76") (name "Net-(ID2-Pad1)") (class "Default")
      (node (ref "ID2") (pin "1") (pinfunction "1_1") (pintype "passive"))
      (node (ref "SV5") (pin "32") (pinfunction "32_32") (pintype "passive"))
    )
    (net (code "77") (name "Net-(ID3-Pad1)") (class "Default")
      (node (ref "ID3") (pin "1") (pinfunction "1_1") (pintype "passive"))
      (node (ref "SV5") (pin "36") (pinfunction "36_36") (pintype "passive"))
    )
    (net (code "78") (name "Net-(ID4-Pad1)") (class "Default")
      (node (ref "ID4") (pin "1") (pinfunction "1_1") (pintype "passive"))
      (node (ref "SV5") (pin "7") (pinfunction "7_7") (pintype "passive"))
    )
    (net (code "79") (name "Net-(ID5-Pad1)") (class "Default")
      (node (ref "ID5") (pin "1") (pinfunction "1_1") (pintype "passive"))
      (node (ref "SV5") (pin "11") (pinfunction "11_11") (pintype "passive"))
    )
    (net (code "80") (name "Net-(ID6-Pad1)") (class "Default")
      (node (ref "ID6") (pin "1") (pinfunction "1_1") (pintype "passive"))
      (node (ref "SV5") (pin "13") (pinfunction "13_13") (pintype "passive"))
    )
    (net (code "81") (name "Net-(ID7-Pad1)") (class "Default")
      (node (ref "ID7") (pin "1") (pinfunction "1_1") (pintype "passive"))
      (node (ref "SV5") (pin "15") (pinfunction "15_15") (pintype "passive"))
    )
    (net (code "82") (name "Net-(ID8-Pad1)") (class "Default")
      (node (ref "ID8") (pin "1") (pinfunction "1_1") (pintype "passive"))
      (node (ref "SV5") (pin "31") (pinfunction "31_31") (pintype "passive"))
    )
    (net (code "83") (name "Net-(ID9-Pad1)") (class "Default")
      (node (ref "ID9") (pin "1") (pinfunction "1_1") (pintype "passive"))
      (node (ref "SV5") (pin "33") (pinfunction "33_33") (pintype "passive"))
    )
    (net (code "84") (name "Net-(ID10-Pad1)") (class "Default")
      (node (ref "ID10") (pin "1") (pinfunction "1_1") (pintype "passive"))
      (node (ref "SV5") (pin "35") (pinfunction "35_35") (pintype "passive"))
    )
    (net (code "85") (name "Net-(ID11-Pad1)") (class "Default")
      (node (ref "ID11") (pin "1") (pinfunction "1_1") (pintype "passive"))
      (node (ref "SV5") (pin "37") (pinfunction "37_37") (pintype "passive"))
    )
    (net (code "86") (name "Net-(ID12-Pad1)") (class "Default")
      (node (ref "ID12") (pin "1") (pinfunction "1_1") (pintype "passive"))
      (node (ref "SV5") (pin "3") (pinfunction "3_3") (pintype "passive"))
    )
    (net (code "87") (name "Net-(ID13-Pad1)") (class "Default")
      (node (ref "ID13") (pin "1") (pinfunction "1_1") (pintype "passive"))
      (node (ref "SV5") (pin "5") (pinfunction "5_5") (pintype "passive"))
    )
    (net (code "88") (name "Net-(ID14-Pad1)") (class "Default")
      (node (ref "ID14") (pin "1") (pinfunction "1_1") (pintype "passive"))
      (node (ref "SV5") (pin "8") (pinfunction "8_8") (pintype "passive"))
    )
    (net (code "89") (name "Net-(ID15-Pad1)") (class "Default")
      (node (ref "ID15") (pin "1") (pinfunction "1_1") (pintype "passive"))
      (node (ref "SV5") (pin "10") (pinfunction "10_10") (pintype "passive"))
    )
    (net (code "90") (name "Net-(U9-PD0_OSC_IN)") (class "Default")
      (node (ref "C8") (pin "1") (pinfunction "1_1") (pintype "passive"))
      (node (ref "U9") (pin "5") (pinfunction "PD0_OSC_IN_5") (pintype "input"))
      (node (ref "Y1") (pin "1") (pinfunction "OSC1_1") (pintype "bidirectional"))
    )
    (net (code "91") (name "Net-(U9-PD1_OSC_OUT)") (class "Default")
      (node (ref "C7") (pin "1") (pinfunction "1_1") (pintype "passive"))
      (node (ref "U9") (pin "6") (pinfunction "PD1_OSC_OUT_6") (pintype "output"))
      (node (ref "Y1") (pin "3") (pinfunction "OSC2_3") (pintype "bidirectional"))
    )
    (net (code "92") (name "unconnected-(SV5-Pad1)") (class "Default")
      (node (ref "SV5") (pin "1") (pinfunction "1_1") (pintype "passive"))
    )
    (net (code "93") (name "unconnected-(SV5-Pad12)") (class "Default")
      (node (ref "SV5") (pin "12") (pinfunction "12_12") (pintype "passive"))
    )
    (net (code "94") (name "unconnected-(SV5-Pad16)") (class "Default")
      (node (ref "SV5") (pin "16") (pinfunction "16_16") (pintype "passive"))
    )
    (net (code "95") (name "unconnected-(SV5-Pad17)") (class "Default")
      (node (ref "SV5") (pin "17") (pinfunction "17_17") (pintype "passive"))
    )
    (net (code "96") (name "unconnected-(SV5-Pad22)") (class "Default")
      (node (ref "SV5") (pin "22") (pinfunction "22_22") (pintype "passive"))
    )
    (net (code "97") (name "unconnected-(SV5-Pad27)") (class "Default")
      (node (ref "SV5") (pin "27") (pinfunction "27_27") (pintype "passive"))
    )
    (net (code "98") (name "unconnected-(SV5-Pad28)") (class "Default")
      (node (ref "SV5") (pin "28") (pinfunction "28_28") (pintype "passive"))
    )
    (net (code "99") (name "unconnected-(SV5-Pad29)") (class "Default")
      (node (ref "SV5") (pin "29") (pinfunction "29_29") (pintype "passive"))
    )
    (net (code "100") (name "unconnected-(SV5-Pad38)") (class "Default")
      (node (ref "SV5") (pin "38") (pinfunction "38_38") (pintype "passive"))
    )
    (net (code "101") (name "unconnected-(SV5-Pad40)") (class "Default")
      (node (ref "SV5") (pin "40") (pinfunction "40_40") (pintype "passive"))
    )
    (net (code "102") (name "unconnected-(U1-*ACX-Pad17)") (class "Default")
      (node (ref "U1") (pin "17") (pinfunction "*ACX_17") (pintype "passive"))
    )
    (net (code "103") (name "unconnected-(U1-ACX-Pad16)") (class "Default")
      (node (ref "U1") (pin "16") (pinfunction "ACX_16") (pintype "passive"))
    )
    (net (code "104") (name "unconnected-(U1-VBIAS-Pad7)") (class "Default")
      (node (ref "U1") (pin "7") (pinfunction "VBIAS_7") (pintype "passive"))
    )
    (net (code "105") (name "unconnected-(U2-*ACX-Pad17)") (class "Default")
      (node (ref "U2") (pin "17") (pinfunction "*ACX_17") (pintype "passive"))
    )
    (net (code "106") (name "unconnected-(U2-ACX-Pad16)") (class "Default")
      (node (ref "U2") (pin "16") (pinfunction "ACX_16") (pintype "passive"))
    )
    (net (code "107") (name "unconnected-(U2-VBIAS-Pad7)") (class "Default")
      (node (ref "U2") (pin "7") (pinfunction "VBIAS_7") (pintype "passive"))
    )
    (net (code "108") (name "unconnected-(U3-*ACX-Pad17)") (class "Default")
      (node (ref "U3") (pin "17") (pinfunction "*ACX_17") (pintype "passive"))
    )
    (net (code "109") (name "unconnected-(U3-ACX-Pad16)") (class "Default")
      (node (ref "U3") (pin "16") (pinfunction "ACX_16") (pintype "passive"))
    )
    (net (code "110") (name "unconnected-(U3-VBIAS-Pad7)") (class "Default")
      (node (ref "U3") (pin "7") (pinfunction "VBIAS_7") (pintype "passive"))
    )
    (net (code "111") (name "unconnected-(U4-*ACX-Pad17)") (class "Default")
      (node (ref "U4") (pin "17") (pinfunction "*ACX_17") (pintype "passive"))
    )
    (net (code "112") (name "unconnected-(U4-ACX-Pad16)") (class "Default")
      (node (ref "U4") (pin "16") (pinfunction "ACX_16") (pintype "passive"))
    )
    (net (code "113") (name "unconnected-(U4-VBIAS-Pad7)") (class "Default")
      (node (ref "U4") (pin "7") (pinfunction "VBIAS_7") (pintype "passive"))
    )
    (net (code "114") (name "unconnected-(U5-*ACX-Pad17)") (class "Default")
      (node (ref "U5") (pin "17") (pinfunction "*ACX_17") (pintype "passive"))
    )
    (net (code "115") (name "unconnected-(U5-ACX-Pad16)") (class "Default")
      (node (ref "U5") (pin "16") (pinfunction "ACX_16") (pintype "passive"))
    )
    (net (code "116") (name "unconnected-(U5-VBIAS-Pad7)") (class "Default")
      (node (ref "U5") (pin "7") (pinfunction "VBIAS_7") (pintype "passive"))
    )
    (net (code "117") (name "unconnected-(U6-*ACX-Pad17)") (class "Default")
      (node (ref "U6") (pin "17") (pinfunction "*ACX_17") (pintype "passive"))
    )
    (net (code "118") (name "unconnected-(U6-ACX-Pad16)") (class "Default")
      (node (ref "U6") (pin "16") (pinfunction "ACX_16") (pintype "passive"))
    )
    (net (code "119") (name "unconnected-(U6-VBIAS-Pad7)") (class "Default")
      (node (ref "U6") (pin "7") (pinfunction "VBIAS_7") (pintype "passive"))
    )
    (net (code "120") (name "unconnected-(U7-*ACX-Pad17)") (class "Default")
      (node (ref "U7") (pin "17") (pinfunction "*ACX_17") (pintype "passive"))
    )
    (net (code "121") (name "unconnected-(U7-ACX-Pad16)") (class "Default")
      (node (ref "U7") (pin "16") (pinfunction "ACX_16") (pintype "passive"))
    )
    (net (code "122") (name "unconnected-(U7-VBIAS-Pad7)") (class "Default")
      (node (ref "U7") (pin "7") (pinfunction "VBIAS_7") (pintype "passive"))
    )
    (net (code "123") (name "unconnected-(U8-*ACX-Pad17)") (class "Default")
      (node (ref "U8") (pin "17") (pinfunction "*ACX_17") (pintype "passive"))
    )
    (net (code "124") (name "unconnected-(U8-ACX-Pad16)") (class "Default")
      (node (ref "U8") (pin "16") (pinfunction "ACX_16") (pintype "passive"))
    )
    (net (code "125") (name "unconnected-(U8-MCLK_OUT-Pad3)") (class "Default")
      (node (ref "U8") (pin "3") (pinfunction "MCLK_OUT_3") (pintype "passive"))
    )
    (net (code "126") (name "unconnected-(U8-VBIAS-Pad7)") (class "Default")
      (node (ref "U8") (pin "7") (pinfunction "VBIAS_7") (pintype "passive"))
    )
    (net (code "127") (name "unconnected-(U9-BOOT0-Pad60)") (class "Default")
      (node (ref "U9") (pin "60") (pinfunction "BOOT0_60") (pintype "passive"))
    )
    (net (code "128") (name "unconnected-(U9-PA4-Pad20)") (class "Default")
      (node (ref "U9") (pin "20") (pinfunction "PA4_20") (pintype "bidirectional"))
    )
    (net (code "129") (name "unconnected-(U9-PA8-Pad41)") (class "Default")
      (node (ref "U9") (pin "41") (pinfunction "PA8_41") (pintype "bidirectional"))
    )
    (net (code "130") (name "unconnected-(U9-PB0-Pad26)") (class "Default")
      (node (ref "U9") (pin "26") (pinfunction "PB0_26") (pintype "bidirectional"))
    )
    (net (code "131") (name "unconnected-(U9-PB1-Pad27)") (class "Default")
      (node (ref "U9") (pin "27") (pinfunction "PB1_27") (pintype "bidirectional"))
    )
    (net (code "132") (name "unconnected-(U9-PB1_2-Pad28)") (class "Default")
      (node (ref "U9") (pin "28") (pinfunction "PB1_2_28") (pintype "bidirectional"))
    )
    (net (code "133") (name "unconnected-(U9-PB6-Pad58)") (class "Default")
      (node (ref "U9") (pin "58") (pinfunction "PB6_58") (pintype "bidirectional"))
    )
    (net (code "134") (name "unconnected-(U9-PB8-Pad61)") (class "Default")
      (node (ref "U9") (pin "61") (pinfunction "PB8_61") (pintype "bidirectional"))
    )
    (net (code "135") (name "unconnected-(U9-PB9-Pad62)") (class "Default")
      (node (ref "U9") (pin "62") (pinfunction "PB9_62") (pintype "bidirectional"))
    )
    (net (code "136") (name "unconnected-(U9-PB10-Pad29)") (class "Default")
      (node (ref "U9") (pin "29") (pinfunction "PB10_29") (pintype "bidirectional"))
    )
    (net (code "137") (name "unconnected-(U9-PB11-Pad30)") (class "Default")
      (node (ref "U9") (pin "30") (pinfunction "PB11_30") (pintype "bidirectional"))
    )
    (net (code "138") (name "unconnected-(U9-PB12-Pad33)") (class "Default")
      (node (ref "U9") (pin "33") (pinfunction "PB12_33") (pintype "bidirectional"))
    )
    (net (code "139") (name "unconnected-(U9-PB13-Pad34)") (class "Default")
      (node (ref "U9") (pin "34") (pinfunction "PB13_34") (pintype "bidirectional"))
    )
    (net (code "140") (name "unconnected-(U9-PB14-Pad35)") (class "Default")
      (node (ref "U9") (pin "35") (pinfunction "PB14_35") (pintype "bidirectional"))
    )
    (net (code "141") (name "unconnected-(U9-PB15-Pad36)") (class "Default")
      (node (ref "U9") (pin "36") (pinfunction "PB15_36") (pintype "bidirectional"))
    )
    (net (code "142") (name "unconnected-(U9-PC4-Pad24)") (class "Default")
      (node (ref "U9") (pin "24") (pinfunction "PC4_24") (pintype "passive"))
    )
    (net (code "143") (name "unconnected-(U9-PC5-Pad25)") (class "Default")
      (node (ref "U9") (pin "25") (pinfunction "PC5_25") (pintype "bidirectional"))
    )
    (net (code "144") (name "unconnected-(U9-PC10-Pad51)") (class "Default")
      (node (ref "U9") (pin "51") (pinfunction "PC10_51") (pintype "bidirectional"))
    )
    (net (code "145") (name "unconnected-(U9-PC11-Pad52)") (class "Default")
      (node (ref "U9") (pin "52") (pinfunction "PC11_52") (pintype "bidirectional"))
    )
    (net (code "146") (name "unconnected-(U9-PC12-Pad53)") (class "Default")
      (node (ref "U9") (pin "53") (pinfunction "PC12_53") (pintype "bidirectional"))
    )
    (net (code "147") (name "unconnected-(U9-PC13-TAMPER-RTC-Pad2)") (class "Default")
      (node (ref "U9") (pin "2") (pinfunction "PC13-TAMPER-RTC_2") (pintype "input"))
    )
    (net (code "148") (name "unconnected-(U9-PC14-OSC32_IN-Pad3)") (class "Default")
      (node (ref "U9") (pin "3") (pinfunction "PC14-OSC32_IN_3") (pintype "input"))
    )
    (net (code "149") (name "unconnected-(U9-PC15-OSC32_OUT-Pad4)") (class "Default")
      (node (ref "U9") (pin "4") (pinfunction "PC15-OSC32_OUT_4") (pintype "output"))
    )
    (net (code "150") (name "unconnected-(U9-PD2-Pad54)") (class "Default")
      (node (ref "U9") (pin "54") (pinfunction "PD2_54") (pintype "bidirectional"))
    )
    (net (code "151") (name "unconnected-(Y2-EN-Pad1)") (class "Default")
      (node (ref "Y2") (pin "1") (pinfunction "EN_1") (pintype "bidirectional"))
    )
  )
)
